# Schematic.net
KiCad netlist of a schematic drawn in Altium Designer
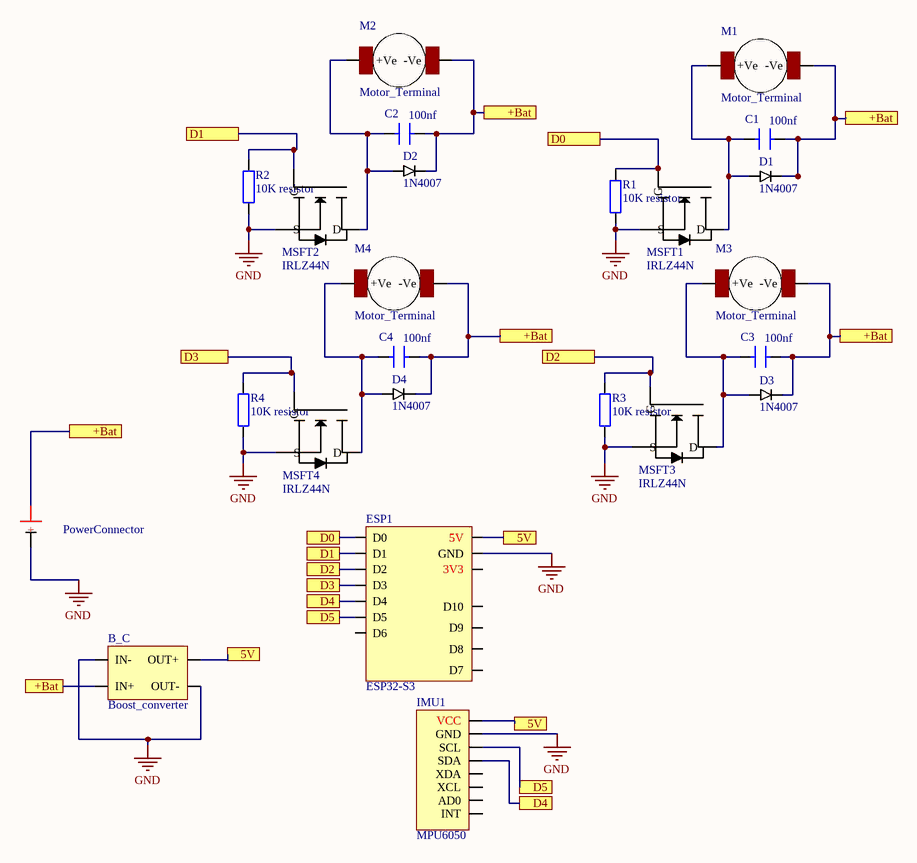
[diagram p0: Schematic.SchDoc]

(export (version "E")
  (design (tool "Eeschema 10.0.6"))
  (components
    (comp (ref "B1")
      (value "PowerConnector")
      (footprint "Power")
      (libsource (lib "SkySCHLIB") (part "PowerConnector"))
    )
    (comp (ref "B_C")
      (value "Boost_converter")
      (footprint "Boost_5V")
      (libsource (lib "SkySCHLIB") (part "Boost_converter"))
    )
    (comp (ref "C1")
      (value "100nf")
      (footprint "TH_Capacitor")
      (libsource (lib "SkySCHLIB") (part "Capacitor"))
    )
    (comp (ref "C2")
      (value "100nf")
      (footprint "TH_Capacitor")
      (libsource (lib "SkySCHLIB") (part "Capacitor"))
    )
    (comp (ref "C3")
      (value "100nf")
      (footprint "TH_Capacitor")
      (libsource (lib "SkySCHLIB") (part "Capacitor"))
    )
    (comp (ref "C4")
      (value "100nf")
      (footprint "TH_Capacitor")
      (libsource (lib "SkySCHLIB") (part "Capacitor"))
    )
    (comp (ref "D1") (value "1N4007") (footprint "TH_Diode") (libsource (lib "SkySCHLIB") (part "1N4007")))
    (comp (ref "D2") (value "1N4007") (footprint "TH_Diode") (libsource (lib "SkySCHLIB") (part "1N4007")))
    (comp (ref "D3") (value "1N4007") (footprint "TH_Diode") (libsource (lib "SkySCHLIB") (part "1N4007")))
    (comp (ref "D4") (value "1N4007") (footprint "TH_Diode") (libsource (lib "SkySCHLIB") (part "1N4007")))
    (comp (ref "ESP1")
      (value "ESP32-S3")
      (footprint "ESP-S3-Seed-Studio")
      (libsource (lib "SkySCHLIB") (part "ESP32-S3"))
    )
    (comp (ref "IMU1")
      (value "MPU6050")
      (footprint "MPU-8-pins")
      (libsource (lib "SkySCHLIB") (part "MPU6050"))
    )
    (comp (ref "M1")
      (value "Motor_Terminal")
      (footprint "Motor Connector")
      (libsource (lib "SkySCHLIB") (part "Motor_Terminal"))
    )
    (comp (ref "M2")
      (value "Motor_Terminal")
      (footprint "Motor Connector")
      (libsource (lib "SkySCHLIB") (part "Motor_Terminal"))
    )
    (comp (ref "M3")
      (value "Motor_Terminal")
      (footprint "Motor Connector")
      (libsource (lib "SkySCHLIB") (part "Motor_Terminal"))
    )
    (comp (ref "M4")
      (value "Motor_Terminal")
      (footprint "Motor Connector")
      (libsource (lib "SkySCHLIB") (part "Motor_Terminal"))
    )
    (comp (ref "MSFT1")
      (value "IRLZ44N")
      (footprint "TH_MOSFET_IRLB8721")
      (libsource (lib "SkySCHLIB") (part "IRLZ44N"))
    )
    (comp (ref "MSFT2")
      (value "IRLZ44N")
      (footprint "TH_MOSFET_IRLB8721")
      (libsource (lib "SkySCHLIB") (part "IRLZ44N"))
    )
    (comp (ref "MSFT3")
      (value "IRLZ44N")
      (footprint "TH_MOSFET_IRLB8721")
      (libsource (lib "SkySCHLIB") (part "IRLZ44N"))
    )
    (comp (ref "MSFT4")
      (value "IRLZ44N")
      (footprint "TH_MOSFET_IRLB8721")
      (libsource (lib "SkySCHLIB") (part "IRLZ44N"))
    )
    (comp (ref "R1")
      (value "10K resistor")
      (footprint "TH_resistor")
      (libsource (lib "SkySCHLIB") (part "R_10K"))
    )
    (comp (ref "R2")
      (value "10K resistor")
      (footprint "TH_resistor")
      (libsource (lib "SkySCHLIB") (part "R_10K"))
    )
    (comp (ref "R3")
      (value "10K resistor")
      (footprint "TH_resistor")
      (libsource (lib "SkySCHLIB") (part "R_10K"))
    )
    (comp (ref "R4")
      (value "10K resistor")
      (footprint "TH_resistor")
      (libsource (lib "SkySCHLIB") (part "R_10K"))
    )
  )
  (nets
    (net (code "1") (name "/+Bat") (class "Default")
      (node (ref "B1") (pin "1") (pinfunction "+_1") (pintype "passive"))
      (node (ref "B_C") (pin "1") (pinfunction "IN+_1") (pintype "passive"))
      (node (ref "C1") (pin "2") (pintype "passive"))
      (node (ref "C2") (pin "2") (pintype "passive"))
      (node (ref "C3") (pin "2") (pintype "passive"))
      (node (ref "C4") (pin "2") (pintype "passive"))
      (node (ref "D1") (pin "2") (pintype "passive"))
      (node (ref "D2") (pin "2") (pintype "passive"))
      (node (ref "D3") (pin "2") (pintype "passive"))
      (node (ref "D4") (pin "2") (pintype "passive"))
      (node (ref "M1") (pin "1") (pinfunction "-Ve_1") (pintype "passive"))
      (node (ref "M2") (pin "1") (pinfunction "-Ve_1") (pintype "passive"))
      (node (ref "M3") (pin "1") (pinfunction "-Ve_1") (pintype "passive"))
      (node (ref "M4") (pin "1") (pinfunction "-Ve_1") (pintype "passive"))
    )
    (net (code "2") (name "/5V") (class "Default")
      (node (ref "B_C") (pin "3") (pinfunction "OUT+_3") (pintype "passive"))
      (node (ref "ESP1") (pin "1") (pinfunction "5V_1") (pintype "passive"))
      (node (ref "IMU1") (pin "1") (pinfunction "VCC_1") (pintype "passive"))
    )
    (net (code "3") (name "/D0") (class "Default")
      (node (ref "ESP1") (pin "8") (pinfunction "D0_8") (pintype "passive"))
      (node (ref "MSFT1") (pin "1") (pinfunction "G_1") (pintype "passive"))
      (node (ref "R1") (pin "1") (pintype "passive"))
    )
    (net (code "4") (name "/D1") (class "Default")
      (node (ref "ESP1") (pin "9") (pinfunction "D1_9") (pintype "passive"))
      (node (ref "MSFT2") (pin "1") (pinfunction "G_1") (pintype "passive"))
      (node (ref "R2") (pin "1") (pintype "passive"))
    )
    (net (code "5") (name "/D2") (class "Default")
      (node (ref "ESP1") (pin "10") (pinfunction "D2_10") (pintype "passive"))
      (node (ref "MSFT3") (pin "1") (pinfunction "G_1") (pintype "passive"))
      (node (ref "R3") (pin "1") (pintype "passive"))
    )
    (net (code "6") (name "/D3") (class "Default")
      (node (ref "ESP1") (pin "11") (pinfunction "D3_11") (pintype "passive"))
      (node (ref "MSFT4") (pin "1") (pinfunction "G_1") (pintype "passive"))
      (node (ref "R4") (pin "1") (pintype "passive"))
    )
    (net (code "7") (name "/D4") (class "Default")
      (node (ref "ESP1") (pin "12") (pinfunction "D4_12") (pintype "passive"))
      (node (ref "IMU1") (pin "4") (pinfunction "SDA_4") (pintype "passive"))
    )
    (net (code "8") (name "/D5") (class "Default")
      (node (ref "ESP1") (pin "13") (pinfunction "D5_13") (pintype "passive"))
      (node (ref "IMU1") (pin "3") (pinfunction "SCL_3") (pintype "passive"))
    )
    (net (code "9") (name "GND") (class "Default")
      (node (ref "B1") (pin "2") (pinfunction "-_2") (pintype "passive"))
      (node (ref "B_C") (pin "2") (pinfunction "IN-_2") (pintype "passive"))
      (node (ref "B_C") (pin "4") (pinfunction "OUT-_4") (pintype "passive"))
      (node (ref "ESP1") (pin "2") (pinfunction "GND_2") (pintype "passive"))
      (node (ref "IMU1") (pin "2") (pinfunction "GND_2") (pintype "passive"))
      (node (ref "MSFT1") (pin "3") (pinfunction "S_3") (pintype "passive"))
      (node (ref "MSFT2") (pin "3") (pinfunction "S_3") (pintype "passive"))
      (node (ref "MSFT3") (pin "3") (pinfunction "S_3") (pintype "passive"))
      (node (ref "MSFT4") (pin "3") (pinfunction "S_3") (pintype "passive"))
      (node (ref "R1") (pin "2") (pintype "passive"))
      (node (ref "R2") (pin "2") (pintype "passive"))
      (node (ref "R3") (pin "2") (pintype "passive"))
      (node (ref "R4") (pin "2") (pintype "passive"))
    )
    (net (code "10") (name "Net-(M1-+Ve)") (class "Default")
      (node (ref "C1") (pin "1") (pintype "passive"))
      (node (ref "D1") (pin "1") (pintype "passive"))
      (node (ref "M1") (pin "2") (pinfunction "+Ve_2") (pintype "passive"))
      (node (ref "MSFT1") (pin "2") (pinfunction "D_2") (pintype "passive"))
    )
    (net (code "11") (name "Net-(M2-+Ve)") (class "Default")
      (node (ref "C2") (pin "1") (pintype "passive"))
      (node (ref "D2") (pin "1") (pintype "passive"))
      (node (ref "M2") (pin "2") (pinfunction "+Ve_2") (pintype "passive"))
      (node (ref "MSFT2") (pin "2") (pinfunction "D_2") (pintype "passive"))
    )
    (net (code "12") (name "Net-(M3-+Ve)") (class "Default")
      (node (ref "C3") (pin "1") (pintype "passive"))
      (node (ref "D3") (pin "1") (pintype "passive"))
      (node (ref "M3") (pin "2") (pinfunction "+Ve_2") (pintype "passive"))
      (node (ref "MSFT3") (pin "2") (pinfunction "D_2") (pintype "passive"))
    )
    (net (code "13") (name "Net-(M4-+Ve)") (class "Default")
      (node (ref "C4") (pin "1") (pintype "passive"))
      (node (ref "D4") (pin "1") (pintype "passive"))
      (node (ref "M4") (pin "2") (pinfunction "+Ve_2") (pintype "passive"))
      (node (ref "MSFT4") (pin "2") (pinfunction "D_2") (pintype "passive"))
    )
    (net (code "14") (name "unconnected-(ESP1-3V3-Pad3)") (class "Default")
      (node (ref "ESP1") (pin "3") (pinfunction "3V3_3") (pintype "passive"))
    )
    (net (code "15") (name "unconnected-(ESP1-D6-Pad14)") (class "Default")
      (node (ref "ESP1") (pin "14") (pinfunction "D6_14") (pintype "passive"))
    )
    (net (code "16") (name "unconnected-(ESP1-D7-Pad7)") (class "Default")
      (node (ref "ESP1") (pin "7") (pinfunction "D7_7") (pintype "passive"))
    )
    (net (code "17") (name "unconnected-(ESP1-D8-Pad6)") (class "Default")
      (node (ref "ESP1") (pin "6") (pinfunction "D8_6") (pintype "passive"))
    )
    (net (code "18") (name "unconnected-(ESP1-D9-Pad5)") (class "Default")
      (node (ref "ESP1") (pin "5") (pinfunction "D9_5") (pintype "passive"))
    )
    (net (code "19") (name "unconnected-(ESP1-D10-Pad4)") (class "Default")
      (node (ref "ESP1") (pin "4") (pinfunction "D10_4") (pintype "passive"))
    )
    (net (code "20") (name "unconnected-(IMU1-AD0-Pad7)") (class "Default")
      (node (ref "IMU1") (pin "7") (pinfunction "AD0_7") (pintype "passive"))
    )
    (net (code "21") (name "unconnected-(IMU1-INT-Pad8)") (class "Default")
      (node (ref "IMU1") (pin "8") (pinfunction "INT_8") (pintype "passive"))
    )
    (net (code "22") (name "unconnected-(IMU1-XCL-Pad6)") (class "Default")
      (node (ref "IMU1") (pin "6") (pinfunction "XCL_6") (pintype "passive"))
    )
    (net (code "23") (name "unconnected-(IMU1-XDA-Pad5)") (class "Default")
      (node (ref "IMU1") (pin "5") (pinfunction "XDA_5") (pintype "passive"))
    )
  )
)
